# untitled.net
KiCad netlist of a schematic drawn in EAGLE
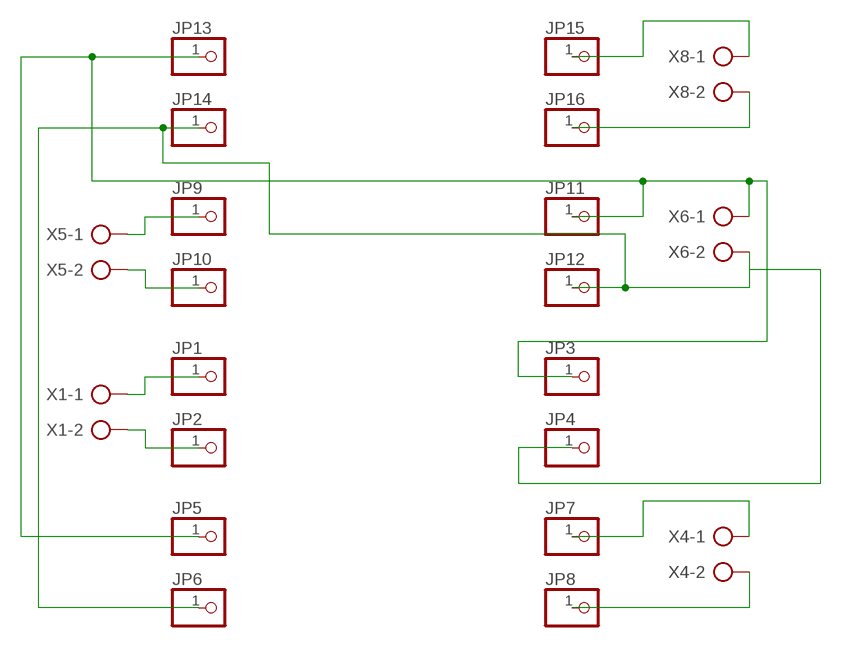
[diagram p0: schematic, sheet 1]

(export (version "E")
  (design (tool "Eeschema 10.0.6"))
  (components
    (comp (ref "JP1")
      (value "PINHD-1X1")
      (footprint "eagle-import:1X01")
      (libsource (lib "eagle-import") (part "PINHD-1X1"))
    )
    (comp (ref "JP2")
      (value "PINHD-1X1")
      (footprint "eagle-import:1X01")
      (libsource (lib "eagle-import") (part "PINHD-1X1"))
    )
    (comp (ref "JP3")
      (value "PINHD-1X1")
      (footprint "eagle-import:1X01")
      (libsource (lib "eagle-import") (part "PINHD-1X1"))
    )
    (comp (ref "JP4")
      (value "PINHD-1X1")
      (footprint "eagle-import:1X01")
      (libsource (lib "eagle-import") (part "PINHD-1X1"))
    )
    (comp (ref "JP5")
      (value "PINHD-1X1")
      (footprint "eagle-import:1X01")
      (libsource (lib "eagle-import") (part "PINHD-1X1"))
    )
    (comp (ref "JP6")
      (value "PINHD-1X1")
      (footprint "eagle-import:1X01")
      (libsource (lib "eagle-import") (part "PINHD-1X1"))
    )
    (comp (ref "JP7")
      (value "PINHD-1X1")
      (footprint "eagle-import:1X01")
      (libsource (lib "eagle-import") (part "PINHD-1X1"))
    )
    (comp (ref "JP8")
      (value "PINHD-1X1")
      (footprint "eagle-import:1X01")
      (libsource (lib "eagle-import") (part "PINHD-1X1"))
    )
    (comp (ref "JP9")
      (value "PINHD-1X1")
      (footprint "eagle-import:1X01")
      (libsource (lib "eagle-import") (part "PINHD-1X1"))
    )
    (comp (ref "JP10")
      (value "PINHD-1X1")
      (footprint "eagle-import:1X01")
      (libsource (lib "eagle-import") (part "PINHD-1X1"))
    )
    (comp (ref "JP11")
      (value "PINHD-1X1")
      (footprint "eagle-import:1X01")
      (libsource (lib "eagle-import") (part "PINHD-1X1"))
    )
    (comp (ref "JP12")
      (value "PINHD-1X1")
      (footprint "eagle-import:1X01")
      (libsource (lib "eagle-import") (part "PINHD-1X1"))
    )
    (comp (ref "JP13")
      (value "PINHD-1X1")
      (footprint "eagle-import:1X01")
      (libsource (lib "eagle-import") (part "PINHD-1X1"))
    )
    (comp (ref "JP14")
      (value "PINHD-1X1")
      (footprint "eagle-import:1X01")
      (libsource (lib "eagle-import") (part "PINHD-1X1"))
    )
    (comp (ref "JP15")
      (value "PINHD-1X1")
      (footprint "eagle-import:1X01")
      (libsource (lib "eagle-import") (part "PINHD-1X1"))
    )
    (comp (ref "JP16")
      (value "PINHD-1X1")
      (footprint "eagle-import:1X01")
      (libsource (lib "eagle-import") (part "PINHD-1X1"))
    )
    (comp (ref "X1")
      (value "AK500/2-H")
      (footprint "eagle-import:AK500_2-H")
      (libsource (lib "eagle-import") (part "AK500/2-H"))
    )
    (comp (ref "X4")
      (value "AK500/2-H")
      (footprint "eagle-import:AK500_2-H")
      (libsource (lib "eagle-import") (part "AK500/2-H"))
    )
    (comp (ref "X5")
      (value "AK500/2-H")
      (footprint "eagle-import:AK500_2-H")
      (libsource (lib "eagle-import") (part "AK500/2-H"))
    )
    (comp (ref "X6")
      (value "AK500/2-H")
      (footprint "eagle-import:AK500_2-H")
      (libsource (lib "eagle-import") (part "AK500/2-H"))
    )
    (comp (ref "X8")
      (value "AK500/2-H")
      (footprint "eagle-import:AK500_2-H")
      (libsource (lib "eagle-import") (part "AK500/2-H"))
    )
  )
  (nets
    (net (code "1") (name "Net-(X1A-KL)") (class "Default")
      (node (ref "JP1") (pin "1") (pinfunction "1_1") (pintype "passive"))
      (node (ref "X1") (pin "1") (pinfunction "KL_1") (pintype "passive"))
    )
    (net (code "2") (name "Net-(X1B-KL)") (class "Default")
      (node (ref "JP2") (pin "1") (pinfunction "1_1") (pintype "passive"))
      (node (ref "X1") (pin "2") (pinfunction "KL_2") (pintype "passive"))
    )
    (net (code "3") (name "Net-(X4A-KL)") (class "Default")
      (node (ref "JP7") (pin "1") (pinfunction "1_1") (pintype "passive"))
      (node (ref "X4") (pin "1") (pinfunction "KL_1") (pintype "passive"))
    )
    (net (code "4") (name "Net-(X4B-KL)") (class "Default")
      (node (ref "JP8") (pin "1") (pinfunction "1_1") (pintype "passive"))
      (node (ref "X4") (pin "2") (pinfunction "KL_2") (pintype "passive"))
    )
    (net (code "5") (name "Net-(X5A-KL)") (class "Default")
      (node (ref "JP9") (pin "1") (pinfunction "1_1") (pintype "passive"))
      (node (ref "X5") (pin "1") (pinfunction "KL_1") (pintype "passive"))
    )
    (net (code "6") (name "Net-(X5B-KL)") (class "Default")
      (node (ref "JP10") (pin "1") (pinfunction "1_1") (pintype "passive"))
      (node (ref "X5") (pin "2") (pinfunction "KL_2") (pintype "passive"))
    )
    (net (code "7") (name "Net-(X6A-KL)") (class "Default")
      (node (ref "JP11") (pin "1") (pinfunction "1_1") (pintype "passive"))
      (node (ref "JP13") (pin "1") (pinfunction "1_1") (pintype "passive"))
      (node (ref "JP3") (pin "1") (pinfunction "1_1") (pintype "passive"))
      (node (ref "JP5") (pin "1") (pinfunction "1_1") (pintype "passive"))
      (node (ref "X6") (pin "1") (pinfunction "KL_1") (pintype "passive"))
    )
    (net (code "8") (name "Net-(X6B-KL)") (class "Default")
      (node (ref "JP12") (pin "1") (pinfunction "1_1") (pintype "passive"))
      (node (ref "JP14") (pin "1") (pinfunction "1_1") (pintype "passive"))
      (node (ref "JP4") (pin "1") (pinfunction "1_1") (pintype "passive"))
      (node (ref "JP6") (pin "1") (pinfunction "1_1") (pintype "passive"))
      (node (ref "X6") (pin "2") (pinfunction "KL_2") (pintype "passive"))
    )
    (net (code "9") (name "Net-(X8A-KL)") (class "Default")
      (node (ref "JP15") (pin "1") (pinfunction "1_1") (pintype "passive"))
      (node (ref "X8") (pin "1") (pinfunction "KL_1") (pintype "passive"))
    )
    (net (code "10") (name "Net-(X8B-KL)") (class "Default")
      (node (ref "JP16") (pin "1") (pinfunction "1_1") (pintype "passive"))
      (node (ref "X8") (pin "2") (pinfunction "KL_2") (pintype "passive"))
    )
  )
)
